# TPS5530RTE_Schematic.net
KiCad netlist of a schematic drawn in Altium Designer
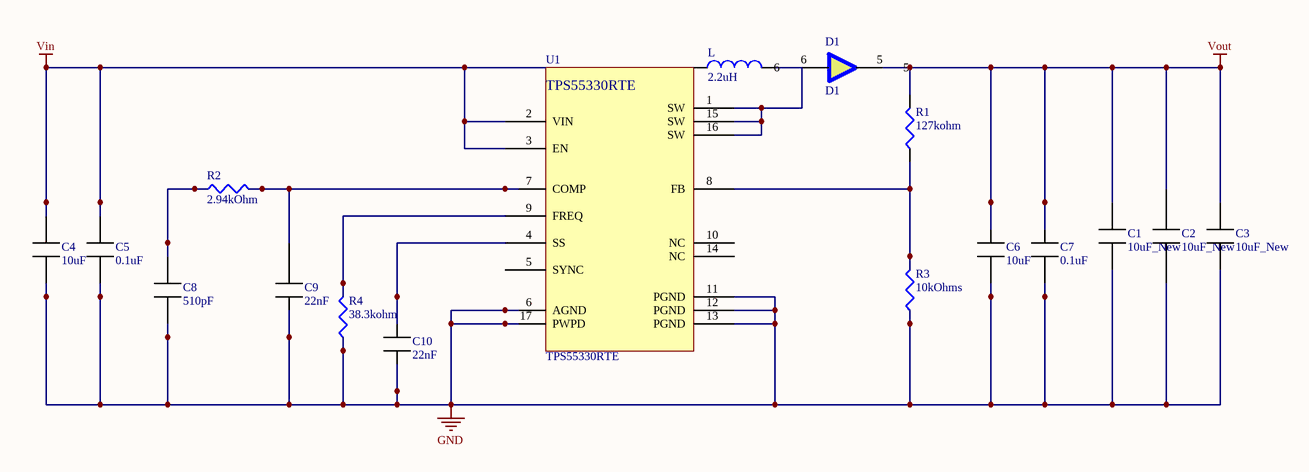
[diagram p0: TPS5530RTE_Schematic.SchDoc]

(export (version "E")
  (design (tool "Eeschema 10.0.6"))
  (components
    (comp (ref "C1")
      (value "10uF_New")
      (footprint "CAPPM7343X310N")
      (description "CAP TANT 10UF 35V 20% 2917")
      (fields
        (field (name "MANUFACTURER") "KEMET")
        (field (name "MANUFACTURER PART NUMBER") "T495D106M035ATE125")
      )
      (libsource (lib "TPS55330RTE_Schematic_Library") (part "T495D106M035ATE125"))
    )
    (comp (ref "C2")
      (value "10uF_New")
      (footprint "CAPPM7343X310N")
      (description "CAP TANT 10UF 35V 20% 2917")
      (fields
        (field (name "MANUFACTURER") "KEMET")
        (field (name "MANUFACTURER PART NUMBER") "T495D106M035ATE125")
      )
      (libsource (lib "TPS55330RTE_Schematic_Library") (part "T495D106M035ATE125"))
    )
    (comp (ref "C3")
      (value "10uF_New")
      (footprint "CAPPM7343X310N")
      (description "CAP TANT 10UF 35V 20% 2917")
      (fields
        (field (name "MANUFACTURER") "KEMET")
        (field (name "MANUFACTURER PART NUMBER") "T495D106M035ATE125")
      )
      (libsource (lib "TPS55330RTE_Schematic_Library") (part "T495D106M035ATE125"))
    )
    (comp (ref "C4")
      (value "10uF")
      (footprint "C/R1206")
      (description "Cap Ceramic 10uF 16V X5R 10% SMD 1206 85C T/R")
      (fields
        (field (name "MANUFACTURER") "Murata")
        (field (name "MANUFACTURER PART NUMBER") "GRM31CR61C106KA88L")
      )
      (libsource (lib "TPS55330RTE_Schematic_Library") (part "GRM31CR61C106KA88L"))
    )
    (comp (ref "C5")
      (value "0.1uF")
      (footprint "C/R0402")
      (description "CAP CER 0.1UF 16V X7R 0402")
      (fields
        (field (name "MANUFACTURER") "Murata")
        (field (name "MANUFACTURER PART NUMBER") "GRM155R71C104KA88D")
      )
      (libsource (lib "TPS55330RTE_Schematic_Library") (part "GRM155R71C104KA88D"))
    )
    (comp (ref "C6")
      (value "10uF")
      (footprint "C/R0805")
      (description "TDK - CGA6P3X7S1H106K250AB - CAP, 10µF, 50V, 10%, X7S, 1210")
      (fields
        (field (name "MANUFACTURER") "TDK")
        (field (name "MANUFACTURER PART NUMBER") "CGA6P3X7S1H106K250AB")
      )
      (libsource (lib "TPS55330RTE_Schematic_Library") (part "CGA6P3X7S1H106K250AB"))
    )
    (comp (ref "C7")
      (value "0.1uF")
      (footprint "C/R0402")
      (description "CAP CER 0.1UF 16V X7R 0402")
      (fields
        (field (name "MANUFACTURER") "Murata")
        (field (name "MANUFACTURER PART NUMBER") "GRM155R71C104KA88D")
      )
      (libsource (lib "TPS55330RTE_Schematic_Library") (part "GRM155R71C104KA88D"))
    )
    (comp (ref "C8")
      (value "510pF")
      (footprint "C/R0402")
      (description "Cap Ceramic 510pF 50V C0G 2% SMD 0402 125C Paper T/R")
      (fields
        (field (name "MANUFACTURER") "Murata")
        (field (name "MANUFACTURER PART NUMBER") "GRM1555C1H511GA01D")
      )
      (libsource (lib "TPS55330RTE_Schematic_Library") (part "GRM1555C1H511GA01D"))
    )
    (comp (ref "C9")
      (value "22nF")
      (footprint "C/R0805")
      (description "TDK - CGA4J2C0G1H223J125AA - KONDENSATOR 0.022µF 50V 5% C0G/NP0 0805")
      (fields
        (field (name "MANUFACTURER") "TDK")
        (field (name "MANUFACTURER PART NUMBER") "CGA4J2C0G1H223J125AA")
      )
      (libsource (lib "TPS55330RTE_Schematic_Library") (part "CGA4J2C0G1H223J125AA"))
    )
    (comp (ref "C10")
      (value "22nF")
      (footprint "C/R0805")
      (description "KEMET 22nF Multilayer Ceramic Capacitor (MLCC) 50V dc 10% X7R dielectric max op. temp. 125C")
      (fields
        (field (name "MANUFACTURER") "KEMET")
        (field (name "MANUFACTURER PART NUMBER") "C0805C223K5RAC")
      )
      (libsource (lib "TPS55330RTE_Schematic_Library") (part "C0805C223K5RAC"))
    )
    (comp (ref "D1")
      (value "D1")
      (footprint "D1")
      (description "DIODE SCHOTTKY 60V 7A POWERDI5")
      (fields (field (name "MANUFACTURER") "Diodes") (field (name "MANUFACTURER PART NUMBER") "PDS760-13"))
      (libsource (lib "TPS55330RTE_Schematic_Library") (part "PDS760-13"))
    )
    (comp (ref "L")
      (value "2.2uH")
      (footprint "L1")
      (description "Fixed Inductors 2.2uH 20%")
      (fields
        (field (name "MANUFACTURER") "Vishay Dale")
        (field (name "MANUFACTURER PART NUMBER") "IHLP2525EZER2R2M01")
      )
      (libsource (lib "TPS55330RTE_Schematic_Library") (part "IHLP2525EZER2R2M01"))
    )
    (comp (ref "R1")
      (value "127kohm")
      (footprint "C/R0805")
      (description "RES SMD 127K OHM 0.1% 1/8W 0805")
      (fields
        (field (name "MANUFACTURER") "Panasonic")
        (field (name "MANUFACTURER PART NUMBER") "ERA-6AEB1273V")
      )
      (libsource (lib "TPS55330RTE_Schematic_Library") (part "ERA-6AEB1273V"))
    )
    (comp (ref "R2")
      (value "2.94kOhm")
      (footprint "C/R0805")
      (description "RES SMD 2.94K OHM 0.1% 1/8W 0805")
      (fields
        (field (name "MANUFACTURER") "Panasonic")
        (field (name "MANUFACTURER PART NUMBER") "ERA-6AEB2941V")
      )
      (libsource (lib "TPS55330RTE_Schematic_Library") (part "ERA-6AEB2941V"))
    )
    (comp (ref "R3")
      (value "10kOhms")
      (footprint "C/R0805")
      (description "Res Thick Film 0805 10K Ohm 1% 0.125W(1/8W) ±100ppm/C Molded SMD Automotive Paper T/R")
      (fields
        (field (name "MANUFACTURER") "Vishay Dale")
        (field (name "MANUFACTURER PART NUMBER") "CRCW080510K0FKEC")
      )
      (libsource (lib "TPS55330RTE_Schematic_Library") (part "CRCW080510K0FKEC"))
    )
    (comp (ref "R4")
      (value "38.3kohm")
      (footprint "C/R0805")
      (description "RES SMD 38.3K OHM 0.1% 1/8W 0805")
      (fields
        (field (name "MANUFACTURER") "Panasonic")
        (field (name "MANUFACTURER PART NUMBER") "ERA-6AEB3832V")
      )
      (libsource (lib "TPS55330RTE_Schematic_Library") (part "ERA-6AEB3832V"))
    )
    (comp (ref "U1")
      (value "TPS55330RTE")
      (footprint "TPS55330")
      (fields
        (field (name "MANUFACTURER") "Texas Instruments")
        (field (name "MANUFACTURER PART NUMBER") "TPS55330RTER")
      )
      (libsource (lib "TPS55330RTE_Schematic_Library") (part "TPS55330RTE"))
    )
  )
  (nets
    (net (code "1") (name "GND") (class "Default")
      (node (ref "C10") (pin "1") (pinfunction "1_1") (pintype "passive"))
      (node (ref "C4") (pin "2") (pinfunction "2_2") (pintype "passive"))
      (node (ref "C5") (pin "2") (pinfunction "2_2") (pintype "passive"))
      (node (ref "C6") (pin "2") (pinfunction "2_2") (pintype "passive"))
      (node (ref "C7") (pin "1") (pinfunction "1_1") (pintype "passive"))
      (node (ref "C8") (pin "2") (pinfunction "2_2") (pintype "passive"))
      (node (ref "C9") (pin "1") (pinfunction "1_1") (pintype "passive"))
      (node (ref "R3") (pin "1") (pinfunction "1_1") (pintype "passive"))
      (node (ref "R4") (pin "1") (pinfunction "1_1") (pintype "passive"))
      (node (ref "U1") (pin "11") (pinfunction "PGND_11") (pintype "passive"))
      (node (ref "U1") (pin "12") (pinfunction "PGND_12") (pintype "passive"))
      (node (ref "U1") (pin "13") (pinfunction "PGND_13") (pintype "passive"))
      (node (ref "U1") (pin "17") (pinfunction "PWPD_17") (pintype "passive"))
      (node (ref "U1") (pin "6") (pinfunction "AGND_6") (pintype "passive"))
    )
    (net (code "2") (name "Net-(C8-Pad1)") (class "Default")
      (node (ref "C8") (pin "1") (pinfunction "1_1") (pintype "passive"))
      (node (ref "R2") (pin "1") (pinfunction "1_1") (pintype "passive"))
    )
    (net (code "3") (name "Net-(L-Pad2)") (class "Default")
      (node (ref "L") (pin "2") (pinfunction "2_2") (pintype "passive"))
      (node (ref "U1") (pin "1") (pinfunction "SW_1") (pintype "passive"))
      (node (ref "U1") (pin "15") (pinfunction "SW_15") (pintype "passive"))
      (node (ref "U1") (pin "16") (pinfunction "SW_16") (pintype "passive"))
    )
    (net (code "4") (name "Net-(U1-COMP)") (class "Default")
      (node (ref "C9") (pin "2") (pinfunction "2_2") (pintype "passive"))
      (node (ref "R2") (pin "2") (pinfunction "2_2") (pintype "passive"))
      (node (ref "U1") (pin "7") (pinfunction "COMP_7") (pintype "passive"))
    )
    (net (code "5") (name "Net-(U1-FB)") (class "Default")
      (node (ref "R1") (pin "1") (pinfunction "1_1") (pintype "passive"))
      (node (ref "R3") (pin "2") (pinfunction "2_2") (pintype "passive"))
      (node (ref "U1") (pin "8") (pinfunction "FB_8") (pintype "passive"))
    )
    (net (code "6") (name "Net-(U1-FREQ)") (class "Default")
      (node (ref "R4") (pin "2") (pinfunction "2_2") (pintype "passive"))
      (node (ref "U1") (pin "9") (pinfunction "FREQ_9") (pintype "passive"))
    )
    (net (code "7") (name "Net-(U1-SS)") (class "Default")
      (node (ref "C10") (pin "2") (pinfunction "2_2") (pintype "passive"))
      (node (ref "U1") (pin "4") (pinfunction "SS_4") (pintype "passive"))
    )
    (net (code "8") (name "Vin") (class "Default")
      (node (ref "C4") (pin "1") (pinfunction "1_1") (pintype "passive"))
      (node (ref "C5") (pin "1") (pinfunction "1_1") (pintype "passive"))
      (node (ref "U1") (pin "2") (pinfunction "VIN_2") (pintype "passive"))
      (node (ref "U1") (pin "3") (pinfunction "EN_3") (pintype "passive"))
    )
    (net (code "9") (name "Vout") (class "Default")
      (node (ref "C6") (pin "1") (pinfunction "1_1") (pintype "passive"))
      (node (ref "C7") (pin "2") (pinfunction "2_2") (pintype "passive"))
      (node (ref "R1") (pin "2") (pinfunction "2_2") (pintype "passive"))
    )
    (net (code "10") (name "unconnected-(C1-Pad3)") (class "Default")
      (node (ref "C1") (pin "3") (pintype "passive"))
    )
    (net (code "11") (name "unconnected-(C1-Pad4)") (class "Default")
      (node (ref "C1") (pin "4") (pintype "passive"))
    )
    (net (code "12") (name "unconnected-(C2-Pad3)") (class "Default")
      (node (ref "C2") (pin "3") (pintype "passive"))
    )
    (net (code "13") (name "unconnected-(C2-Pad4)") (class "Default")
      (node (ref "C2") (pin "4") (pintype "passive"))
    )
    (net (code "14") (name "unconnected-(C3-Pad3)") (class "Default")
      (node (ref "C3") (pin "3") (pintype "passive"))
    )
    (net (code "15") (name "unconnected-(C3-Pad4)") (class "Default")
      (node (ref "C3") (pin "4") (pintype "passive"))
    )
    (net (code "16") (name "unconnected-(D1-Pad5)") (class "Default")
      (node (ref "D1") (pin "5") (pinfunction "5_5") (pintype "passive"))
    )
    (net (code "17") (name "unconnected-(D1-Pad6)") (class "Default")
      (node (ref "D1") (pin "6") (pinfunction "6_6") (pintype "passive"))
    )
    (net (code "18") (name "unconnected-(L-Pad1)") (class "Default")
      (node (ref "L") (pin "1") (pinfunction "1_1") (pintype "passive"))
    )
    (net (code "19") (name "unconnected-(U1-NC-Pad10)") (class "Default")
      (node (ref "U1") (pin "10") (pinfunction "NC_10") (pintype "passive"))
    )
    (net (code "20") (name "unconnected-(U1-NC-Pad14)") (class "Default")
      (node (ref "U1") (pin "14") (pinfunction "NC_14") (pintype "passive"))
    )
    (net (code "21") (name "unconnected-(U1-SYNC-Pad5)") (class "Default")
      (node (ref "U1") (pin "5") (pinfunction "SYNC_5") (pintype "passive"))
    )
  )
)
